# Transient_tester_DC_supply_r2B1.net
KiCad netlist of a schematic drawn in EAGLE
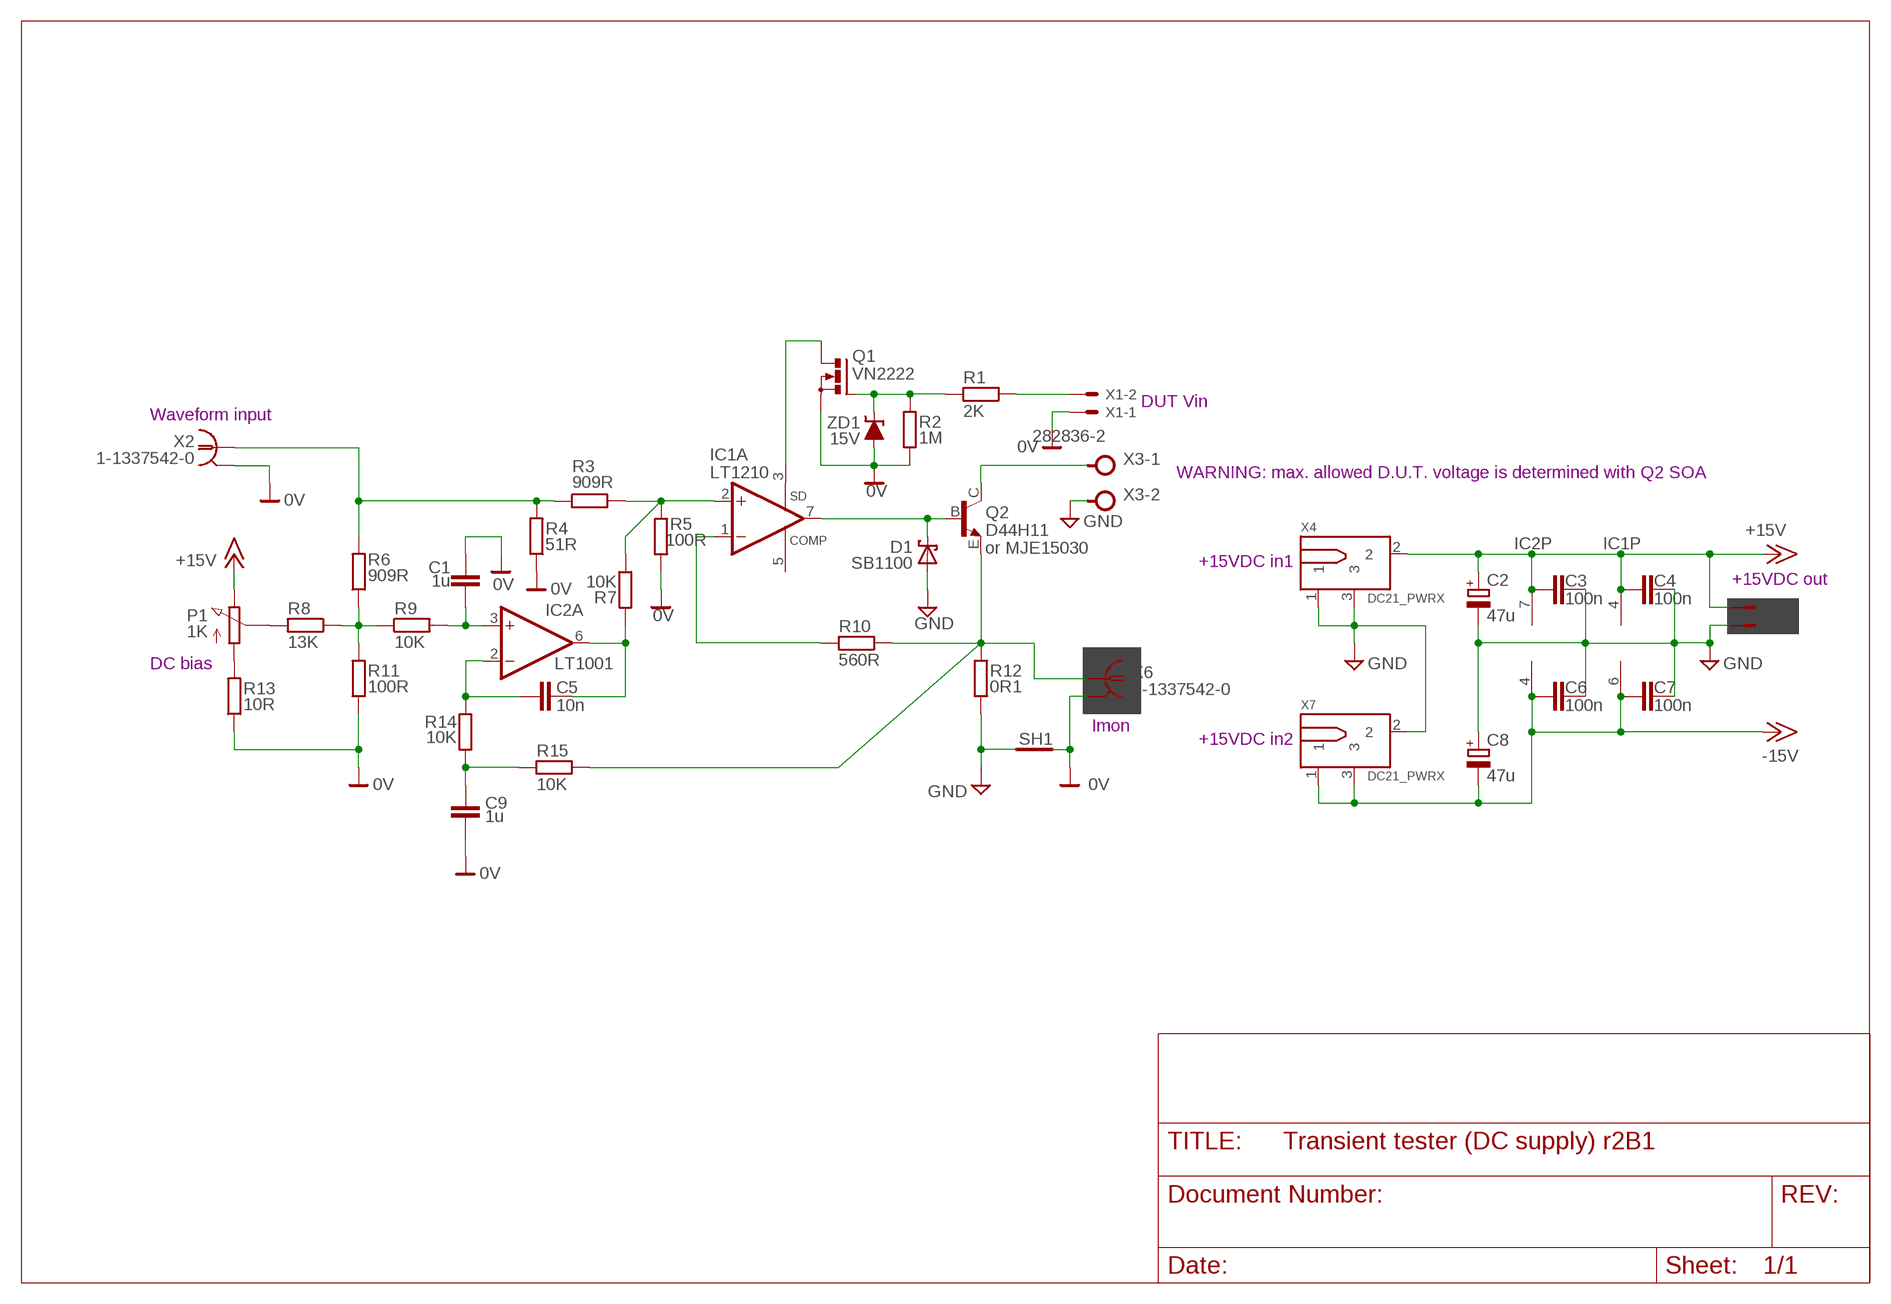
[diagram p0: schematic, sheet 1]

(export (version "E")
  (design (tool "Eeschema 10.0.6"))
  (components
    (comp (ref "C1")
      (value "1u")
      (footprint "eagle-import:C050-075X075")
      (libsource (lib "eagle-import") (part "C-EU050-075X075"))
    )
    (comp (ref "C2")
      (value "47u")
      (footprint "eagle-import:ECAP2.5_7")
      (libsource (lib "eagle-import") (part "ECAP2.5G_7MM"))
    )
    (comp (ref "C3")
      (value "100n")
      (footprint "eagle-import:C050-025X075")
      (libsource (lib "eagle-import") (part "C-EU050-025X075"))
    )
    (comp (ref "C4")
      (value "100n")
      (footprint "eagle-import:C050-025X075")
      (libsource (lib "eagle-import") (part "C-EU050-025X075"))
    )
    (comp (ref "C5")
      (value "10n")
      (footprint "eagle-import:C050-025X075")
      (libsource (lib "eagle-import") (part "C-EU050-025X075"))
    )
    (comp (ref "C6")
      (value "100n")
      (footprint "eagle-import:C050-025X075")
      (libsource (lib "eagle-import") (part "C-EU050-025X075"))
    )
    (comp (ref "C7")
      (value "100n")
      (footprint "eagle-import:C050-025X075")
      (libsource (lib "eagle-import") (part "C-EU050-025X075"))
    )
    (comp (ref "C8")
      (value "47u")
      (footprint "eagle-import:ECAP2.5_7")
      (libsource (lib "eagle-import") (part "ECAP2.5G_7MM"))
    )
    (comp (ref "C9")
      (value "1u")
      (footprint "eagle-import:C050-075X075")
      (libsource (lib "eagle-import") (part "C-EU050-075X075"))
    )
    (comp (ref "D1")
      (value "SB1100")
      (footprint "eagle-import:DO34_10")
      (libsource (lib "eagle-import") (part "SCHOTTKY"))
    )
    (comp (ref "IC1")
      (value "LT1210")
      (footprint "eagle-import:TO220-7")
      (libsource (lib "eagle-import") (part "LT1210"))
    )
    (comp (ref "IC2")
      (value "LT1001")
      (footprint "eagle-import:DIL08D")
      (libsource (lib "eagle-import") (part "LT1001"))
    )
    (comp (ref "P1")
      (value "1K")
      (footprint "eagle-import:BOURNS_POT91")
      (libsource (lib "eagle-import") (part "POTENTIOMETER"))
    )
    (comp (ref "Q1")
      (value "VN2222")
      (footprint "eagle-import:TO92-SGD")
      (libsource (lib "eagle-import") (part "2N7000"))
    )
    (comp (ref "Q2")
      (value "D44H11")
      (footprint "eagle-import:TO220BV")
      (libsource (lib "eagle-import") (part "D44H11"))
    )
    (comp (ref "R1")
      (value "2K")
      (footprint "eagle-import:0204_5")
      (libsource (lib "eagle-import") (part "R-EU_0204/5"))
    )
    (comp (ref "R2")
      (value "1M")
      (footprint "eagle-import:0204_5")
      (libsource (lib "eagle-import") (part "R-EU_0204/5"))
    )
    (comp (ref "R3")
      (value "909R")
      (footprint "eagle-import:0207_10")
      (libsource (lib "eagle-import") (part "R-EU_0207/10"))
    )
    (comp (ref "R4")
      (value "51R")
      (footprint "eagle-import:0204_5")
      (libsource (lib "eagle-import") (part "R-EU_0204/5"))
    )
    (comp (ref "R5")
      (value "100R")
      (footprint "eagle-import:0204_5")
      (libsource (lib "eagle-import") (part "R-EU_0204/5"))
    )
    (comp (ref "R6")
      (value "909R")
      (footprint "eagle-import:0207_10")
      (libsource (lib "eagle-import") (part "R-EU_0207/10"))
    )
    (comp (ref "R7")
      (value "10K")
      (footprint "eagle-import:0204_5")
      (libsource (lib "eagle-import") (part "R-EU_0204/5"))
    )
    (comp (ref "R8")
      (value "13K")
      (footprint "eagle-import:0204_5")
      (libsource (lib "eagle-import") (part "R-EU_0204/5"))
    )
    (comp (ref "R9")
      (value "10K")
      (footprint "eagle-import:0204_5")
      (libsource (lib "eagle-import") (part "R-EU_0204/5"))
    )
    (comp (ref "R10")
      (value "560R")
      (footprint "eagle-import:0204_5")
      (libsource (lib "eagle-import") (part "R-EU_0204/5"))
    )
    (comp (ref "R11")
      (value "100R")
      (footprint "eagle-import:0204_5")
      (libsource (lib "eagle-import") (part "R-EU_0204/5"))
    )
    (comp (ref "R12")
      (value "0R1")
      (footprint "eagle-import:OAR1+2512")
      (libsource (lib "eagle-import") (part "R_EU_OAR1+2512"))
    )
    (comp (ref "R13")
      (value "10R")
      (footprint "eagle-import:0204_5")
      (libsource (lib "eagle-import") (part "R-EU_0204/5"))
    )
    (comp (ref "R14")
      (value "10K")
      (footprint "eagle-import:0204_5")
      (libsource (lib "eagle-import") (part "R-EU_0204/5"))
    )
    (comp (ref "R15")
      (value "10K")
      (footprint "eagle-import:0204_5")
      (libsource (lib "eagle-import") (part "R-EU_0204/5"))
    )
    (comp (ref "SH1")
      (value "SHORTH")
      (footprint "eagle-import:SHORT_2")
      (libsource (lib "eagle-import") (part "SHORTH"))
    )
    (comp (ref "X1")
      (value "22-23-2021")
      (footprint "eagle-import:22-23-2021")
      (fields (field (name "MF") "MOLEX"))
      (libsource (lib "eagle-import") (part "22-23-2021"))
    )
    (comp (ref "X2")
      (value "1-1337542-0")
      (footprint "eagle-import:AMP_227161")
      (fields (field (name "MF") "TYCO ELECTRONICS") (field (name "MPN") "1-227161"))
      (libsource (lib "eagle-import") (part "?2271611--0"))
    )
    (comp (ref "X3")
      (value "282836-2")
      (footprint "eagle-import:TBLOCK5.0_2")
      (libsource (lib "eagle-import") (part "TBLOCK5.0_2A"))
    )
    (comp (ref "X4")
      (value "DC21_PWRX")
      (footprint "eagle-import:DC-21MM")
      (libsource (lib "eagle-import") (part "DC21_PWRX"))
    )
    (comp (ref "X5")
      (value "22-23-2021")
      (footprint "eagle-import:22-23-2021")
      (fields
        (field (name "MF") "MOLEX")
        (field (name "MF_1") "MOLEX")
        (field (name "MPN") "22-23-2021")
        (field (name "OC_FARNELL") "1462926")
        (field (name "OC_NEWARK") "25C3832")
      )
      (libsource (lib "eagle-import") (part "22-23-2021"))
    )
    (comp (ref "X6")
      (value "1-1337542-0")
      (footprint "eagle-import:AMP_227161")
      (fields (field (name "MF") "TYCO ELECTRONICS") (field (name "MPN") "1-227161"))
      (libsource (lib "eagle-import") (part "?2271611--0"))
    )
    (comp (ref "X7")
      (value "DC21_PWRX")
      (footprint "eagle-import:DC-21MM")
      (libsource (lib "eagle-import") (part "DC21_PWRX"))
    )
    (comp (ref "ZD1")
      (value "15V")
      (footprint "eagle-import:DO34-ZD")
      (libsource (lib "eagle-import") (part "ZENER-DIODE"))
    )
  )
  (nets
    (net (code "1") (name "+15V") (class "Default")
      (node (ref "C2") (pin "+") (pinfunction "+_+") (pintype "passive"))
      (node (ref "C3") (pin "2") (pinfunction "2_2") (pintype "passive"))
      (node (ref "C4") (pin "2") (pinfunction "2_2") (pintype "passive"))
      (node (ref "IC1") (pin "4") (pinfunction "V+_4") (pintype "power_in"))
      (node (ref "IC2") (pin "7") (pinfunction "V+_7") (pintype "power_in"))
      (node (ref "P1") (pin "1") (pinfunction "E_1") (pintype "passive"))
      (node (ref "X4") (pin "2") (pinfunction "2_2") (pintype "power_in"))
      (node (ref "X5") (pin "1") (pinfunction "S_1") (pintype "passive"))
    )
    (net (code "2") (name "-15V") (class "Default")
      (node (ref "C6") (pin "2") (pinfunction "2_2") (pintype "passive"))
      (node (ref "C7") (pin "2") (pinfunction "2_2") (pintype "passive"))
      (node (ref "C8") (pin "-") (pinfunction "-_-") (pintype "passive"))
      (node (ref "IC1") (pin "6") (pinfunction "V-_6") (pintype "power_in"))
      (node (ref "IC2") (pin "4") (pinfunction "V-_4") (pintype "power_in"))
      (node (ref "X7") (pin "1") (pinfunction "1_1") (pintype "power_in"))
      (node (ref "X7") (pin "3") (pinfunction "3_3") (pintype "power_in"))
    )
    (net (code "3") (name "0V") (class "Default")
      (node (ref "C1") (pin "1") (pinfunction "1_1") (pintype "passive"))
      (node (ref "C9") (pin "2") (pinfunction "2_2") (pintype "passive"))
      (node (ref "Q1") (pin "S") (pinfunction "S_S") (pintype "passive"))
      (node (ref "R11") (pin "1") (pinfunction "1_1") (pintype "passive"))
      (node (ref "R13") (pin "1") (pinfunction "1_1") (pintype "passive"))
      (node (ref "R2") (pin "1") (pinfunction "1_1") (pintype "passive"))
      (node (ref "R4") (pin "1") (pinfunction "1_1") (pintype "passive"))
      (node (ref "R5") (pin "2") (pinfunction "2_2") (pintype "passive"))
      (node (ref "SH1") (pin "2") (pinfunction "GND_B_2") (pintype "bidirectional"))
      (node (ref "X1") (pin "1") (pinfunction "S_1") (pintype "passive"))
      (node (ref "X2") (pin "2") (pinfunction "GND_2") (pintype "power_in"))
      (node (ref "X6") (pin "2") (pinfunction "GND_2") (pintype "power_in"))
      (node (ref "ZD1") (pin "A") (pinfunction "A_A") (pintype "passive"))
    )
    (net (code "4") (name "GND") (class "Default")
      (node (ref "C2") (pin "-") (pinfunction "-_-") (pintype "passive"))
      (node (ref "C3") (pin "1") (pinfunction "1_1") (pintype "passive"))
      (node (ref "C4") (pin "1") (pinfunction "1_1") (pintype "passive"))
      (node (ref "C6") (pin "1") (pinfunction "1_1") (pintype "passive"))
      (node (ref "C7") (pin "1") (pinfunction "1_1") (pintype "passive"))
      (node (ref "C8") (pin "+") (pinfunction "+_+") (pintype "passive"))
      (node (ref "D1") (pin "A") (pinfunction "A_A") (pintype "passive"))
      (node (ref "R12") (pin "1") (pinfunction "1_1") (pintype "passive"))
      (node (ref "R12") (pin "1.1") (pinfunction "1_1.1") (pintype "passive"))
      (node (ref "SH1") (pin "1") (pinfunction "GND_A_1") (pintype "bidirectional"))
      (node (ref "X3") (pin "2") (pinfunction "1_2") (pintype "bidirectional"))
      (node (ref "X4") (pin "1") (pinfunction "1_1") (pintype "power_in"))
      (node (ref "X4") (pin "3") (pinfunction "3_3") (pintype "power_in"))
      (node (ref "X5") (pin "2") (pinfunction "S_2") (pintype "passive"))
      (node (ref "X7") (pin "2") (pinfunction "2_2") (pintype "power_in"))
    )
    (net (code "5") (name "Net-(C9-Pad1)") (class "Default")
      (node (ref "C9") (pin "1") (pinfunction "1_1") (pintype "passive"))
      (node (ref "R14") (pin "2") (pinfunction "2_2") (pintype "passive"))
      (node (ref "R15") (pin "1") (pinfunction "1_1") (pintype "passive"))
    )
    (net (code "6") (name "Net-(IC1A-+IN)") (class "Default")
      (node (ref "IC1") (pin "2") (pinfunction "+IN_2") (pintype "input"))
      (node (ref "R3") (pin "2") (pinfunction "2_2") (pintype "passive"))
      (node (ref "R5") (pin "1") (pinfunction "1_1") (pintype "passive"))
      (node (ref "R7") (pin "1") (pinfunction "1_1") (pintype "passive"))
    )
    (net (code "7") (name "Net-(IC1A--IN)") (class "Default")
      (node (ref "IC1") (pin "1") (pinfunction "-IN_1") (pintype "input"))
      (node (ref "R10") (pin "2") (pinfunction "2_2") (pintype "passive"))
    )
    (net (code "8") (name "Net-(IC1A-OUT)") (class "Default")
      (node (ref "D1") (pin "C") (pinfunction "C_C") (pintype "passive"))
      (node (ref "IC1") (pin "7") (pinfunction "OUT_7") (pintype "output"))
      (node (ref "Q2") (pin "B") (pinfunction "B_B") (pintype "passive"))
    )
    (net (code "9") (name "Net-(IC1A-SD)") (class "Default")
      (node (ref "IC1") (pin "3") (pinfunction "SD_3") (pintype "input"))
      (node (ref "Q1") (pin "D") (pinfunction "D_D") (pintype "passive"))
    )
    (net (code "10") (name "Net-(IC2A-+IN)") (class "Default")
      (node (ref "C1") (pin "2") (pinfunction "2_2") (pintype "passive"))
      (node (ref "IC2") (pin "3") (pinfunction "+IN_3") (pintype "input"))
      (node (ref "R9") (pin "2") (pinfunction "2_2") (pintype "passive"))
    )
    (net (code "11") (name "Net-(IC2A--IN)") (class "Default")
      (node (ref "C5") (pin "2") (pinfunction "2_2") (pintype "passive"))
      (node (ref "IC2") (pin "2") (pinfunction "-IN_2") (pintype "input"))
      (node (ref "R14") (pin "1") (pinfunction "1_1") (pintype "passive"))
    )
    (net (code "12") (name "Net-(IC2A-OUT)") (class "Default")
      (node (ref "C5") (pin "1") (pinfunction "1_1") (pintype "passive"))
      (node (ref "IC2") (pin "6") (pinfunction "OUT_6") (pintype "output"))
      (node (ref "R7") (pin "2") (pinfunction "2_2") (pintype "passive"))
    )
    (net (code "13") (name "Net-(P1-A)") (class "Default")
      (node (ref "P1") (pin "3") (pinfunction "A_3") (pintype "passive"))
      (node (ref "R13") (pin "2") (pinfunction "2_2") (pintype "passive"))
    )
    (net (code "14") (name "Net-(P1-S)") (class "Default")
      (node (ref "P1") (pin "2") (pinfunction "S_2") (pintype "passive"))
      (node (ref "R8") (pin "2") (pinfunction "2_2") (pintype "passive"))
    )
    (net (code "15") (name "Net-(Q1-PadG)") (class "Default")
      (node (ref "Q1") (pin "G") (pinfunction "G_G") (pintype "passive"))
      (node (ref "R1") (pin "2") (pinfunction "2_2") (pintype "passive"))
      (node (ref "R2") (pin "2") (pinfunction "2_2") (pintype "passive"))
      (node (ref "ZD1") (pin "C") (pinfunction "C_C") (pintype "passive"))
    )
    (net (code "16") (name "Net-(Q2-PadC)") (class "Default")
      (node (ref "Q2") (pin "C") (pinfunction "C_C") (pintype "passive"))
      (node (ref "X3") (pin "1") (pinfunction "1_1") (pintype "bidirectional"))
    )
    (net (code "17") (name "Net-(Q2-PadE)") (class "Default")
      (node (ref "Q2") (pin "E") (pinfunction "E_E") (pintype "passive"))
      (node (ref "R10") (pin "1") (pinfunction "1_1") (pintype "passive"))
      (node (ref "R12") (pin "2") (pinfunction "2_2") (pintype "passive"))
      (node (ref "R12") (pin "2.1") (pinfunction "2_2.1") (pintype "passive"))
      (node (ref "R15") (pin "2") (pinfunction "2_2") (pintype "passive"))
      (node (ref "X6") (pin "1") (pinfunction "1_1") (pintype "passive"))
    )
    (net (code "18") (name "Net-(R3-Pad1)") (class "Default")
      (node (ref "R3") (pin "1") (pinfunction "1_1") (pintype "passive"))
      (node (ref "R4") (pin "2") (pinfunction "2_2") (pintype "passive"))
      (node (ref "R6") (pin "2") (pinfunction "2_2") (pintype "passive"))
      (node (ref "X2") (pin "1") (pinfunction "1_1") (pintype "passive"))
    )
    (net (code "19") (name "Net-(R11-Pad2)") (class "Default")
      (node (ref "R11") (pin "2") (pinfunction "2_2") (pintype "passive"))
      (node (ref "R6") (pin "1") (pinfunction "1_1") (pintype "passive"))
      (node (ref "R8") (pin "1") (pinfunction "1_1") (pintype "passive"))
      (node (ref "R9") (pin "1") (pinfunction "1_1") (pintype "passive"))
    )
    (net (code "20") (name "Net-(X1B-S)") (class "Default")
      (node (ref "R1") (pin "1") (pinfunction "1_1") (pintype "passive"))
      (node (ref "X1") (pin "2") (pinfunction "S_2") (pintype "passive"))
    )
    (net (code "21") (name "unconnected-(IC1A-COMP-Pad5)") (class "Default")
      (node (ref "IC1") (pin "5") (pinfunction "COMP_5") (pintype "input"))
    )
  )
)
